# mezzanine_card.net
KiCad netlist of a schematic drawn in Altium Designer
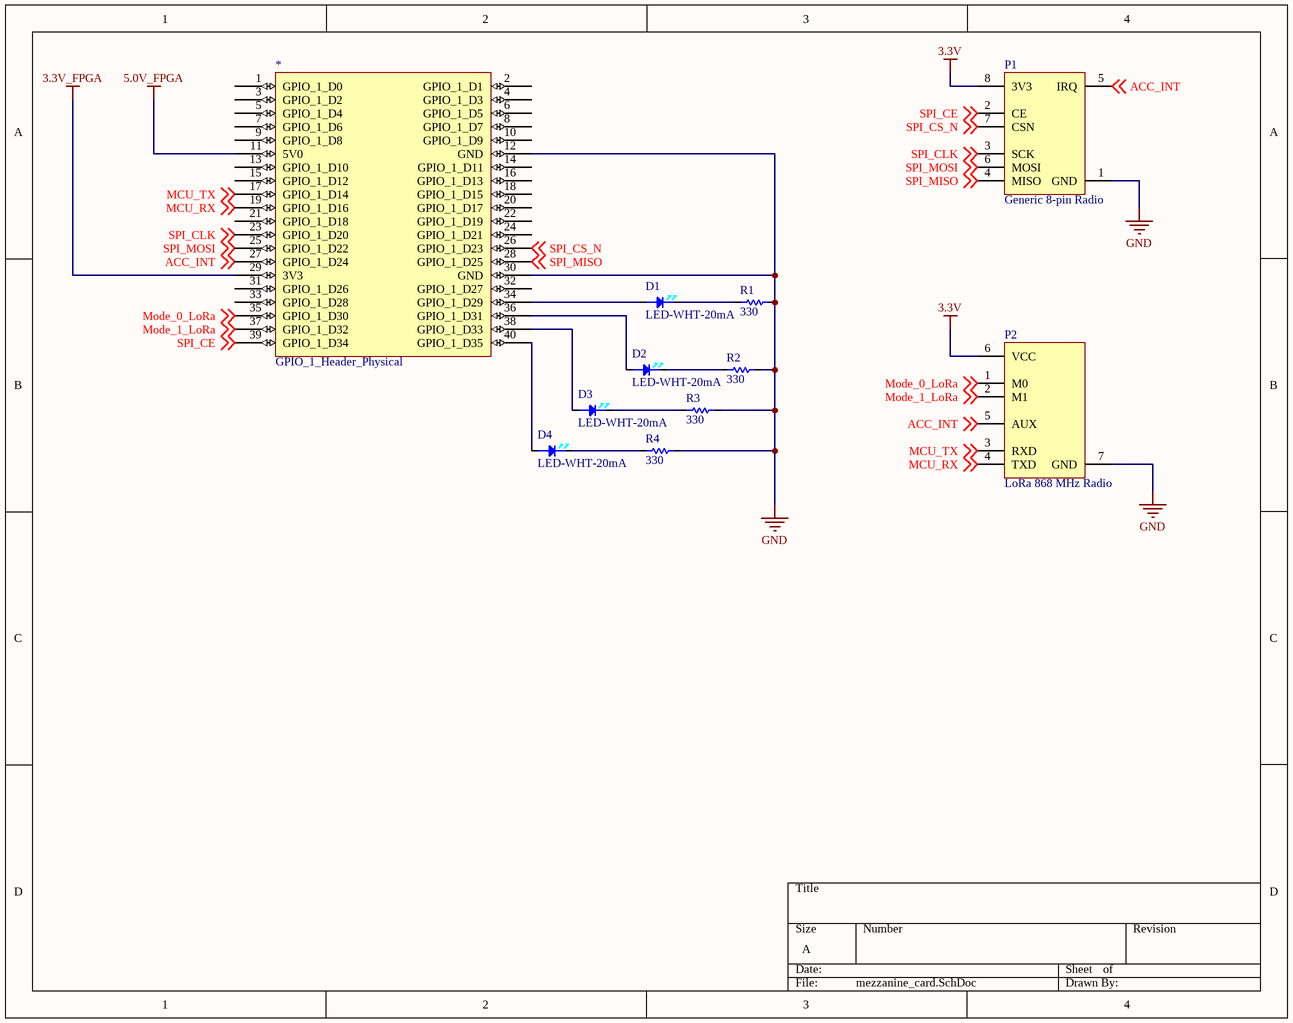
[diagram p0: mezzanine_card.SchDoc]

(export (version "E")
  (design (tool "Eeschema 10.0.6"))
  (components
    (comp (ref "*")
      (value "GPIO_1_Header_Physical")
      (libsource (lib "de0_soc") (part "GPIO_1_Header_Physical"))
    )
    (comp (ref "D1")
      (value "LED-WHT-20mA")
      (footprint "LED-0805")
      (description "2.2V, 0805")
      (libsource (lib "passive") (part "LED-WHT-20mA"))
    )
    (comp (ref "D2")
      (value "LED-WHT-20mA")
      (footprint "LED-0805")
      (description "2.2V, 0805")
      (libsource (lib "passive") (part "LED-WHT-20mA"))
    )
    (comp (ref "D3")
      (value "LED-WHT-20mA")
      (footprint "LED-0805")
      (description "2.2V, 0805")
      (libsource (lib "passive") (part "LED-WHT-20mA"))
    )
    (comp (ref "D4")
      (value "LED-WHT-20mA")
      (footprint "LED-0805")
      (description "2.2V, 0805")
      (libsource (lib "passive") (part "LED-WHT-20mA"))
    )
    (comp (ref "P1")
      (value "Generic 8-pin Radio")
      (footprint "2x4 Radio")
      (description "SPI Interface, 0.1\" Pitch 2x4")
      (libsource (lib "connector") (part "Generic 8-pin Radio"))
    )
    (comp (ref "P2")
      (value "LoRa 868 MHz Radio")
      (footprint "LoRa Breakout")
      (description "UART Interface, 0.1\" Pitch")
      (libsource (lib "connector") (part "868 MHz SX1276 LoRa Breakout"))
    )
    (comp (ref "R1")
      (value "330")
      (footprint "RES-0805")
      (description "0805")
      (libsource (lib "passive") (part "RES-330-1/8W"))
    )
    (comp (ref "R2")
      (value "330")
      (footprint "RES-0805")
      (description "0805")
      (libsource (lib "passive") (part "RES-330-1/8W"))
    )
    (comp (ref "R3")
      (value "330")
      (footprint "RES-0805")
      (description "0805")
      (libsource (lib "passive") (part "RES-330-1/8W"))
    )
    (comp (ref "R4")
      (value "330")
      (footprint "RES-0805")
      (description "0805")
      (libsource (lib "passive") (part "RES-330-1/8W"))
    )
  )
  (nets
    (net (code "1") (name "3.3V") (class "Default")
      (node (ref "P1") (pin "8") (pinfunction "3V3_8") (pintype "passive"))
      (node (ref "P2") (pin "6") (pinfunction "VCC_6") (pintype "passive"))
    )
    (net (code "2") (name "3.3V_FPGA") (class "Default")
      (node (ref "*") (pin "29") (pinfunction "3V3_29") (pintype "bidirectional"))
    )
    (net (code "3") (name "5.0V_FPGA") (class "Default")
      (node (ref "*") (pin "11") (pinfunction "5V0_11") (pintype "bidirectional"))
    )
    (net (code "4") (name "ACC_INT") (class "Default")
      (node (ref "*") (pin "27") (pinfunction "GPIO_1_D24_27") (pintype "bidirectional"))
      (node (ref "P1") (pin "5") (pinfunction "IRQ_5") (pintype "passive"))
      (node (ref "P2") (pin "5") (pinfunction "AUX_5") (pintype "passive"))
    )
    (net (code "5") (name "GND") (class "Default")
      (node (ref "*") (pin "12") (pinfunction "GND_12") (pintype "bidirectional"))
      (node (ref "*") (pin "30") (pinfunction "GND_30") (pintype "bidirectional"))
      (node (ref "P1") (pin "1") (pinfunction "GND_1") (pintype "passive"))
      (node (ref "P2") (pin "7") (pinfunction "GND_7") (pintype "passive"))
      (node (ref "R1") (pin "2") (pinfunction "2_2") (pintype "passive"))
      (node (ref "R2") (pin "2") (pinfunction "2_2") (pintype "passive"))
      (node (ref "R3") (pin "2") (pinfunction "2_2") (pintype "passive"))
      (node (ref "R4") (pin "2") (pinfunction "2_2") (pintype "passive"))
    )
    (net (code "6") (name "MCU_RX") (class "Default")
      (node (ref "*") (pin "19") (pinfunction "GPIO_1_D16_19") (pintype "bidirectional"))
      (node (ref "P2") (pin "4") (pinfunction "TXD_4") (pintype "passive"))
    )
    (net (code "7") (name "MCU_TX") (class "Default")
      (node (ref "*") (pin "17") (pinfunction "GPIO_1_D14_17") (pintype "bidirectional"))
      (node (ref "P2") (pin "3") (pinfunction "RXD_3") (pintype "passive"))
    )
    (net (code "8") (name "Mode_0_LoRa") (class "Default")
      (node (ref "*") (pin "35") (pinfunction "GPIO_1_D30_35") (pintype "bidirectional"))
      (node (ref "P2") (pin "1") (pinfunction "M0_1") (pintype "passive"))
    )
    (net (code "9") (name "Mode_1_LoRa") (class "Default")
      (node (ref "*") (pin "37") (pinfunction "GPIO_1_D32_37") (pintype "bidirectional"))
      (node (ref "P2") (pin "2") (pinfunction "M1_2") (pintype "passive"))
    )
    (net (code "10") (name "Net-(*-GPIO_1_D29)") (class "Default")
      (node (ref "*") (pin "34") (pinfunction "GPIO_1_D29_34") (pintype "bidirectional"))
      (node (ref "D1") (pin "1") (pinfunction "CT_1") (pintype "passive"))
    )
    (net (code "11") (name "Net-(*-GPIO_1_D31)") (class "Default")
      (node (ref "*") (pin "36") (pinfunction "GPIO_1_D31_36") (pintype "bidirectional"))
      (node (ref "D2") (pin "1") (pinfunction "CT_1") (pintype "passive"))
    )
    (net (code "12") (name "Net-(*-GPIO_1_D33)") (class "Default")
      (node (ref "*") (pin "38") (pinfunction "GPIO_1_D33_38") (pintype "bidirectional"))
      (node (ref "D3") (pin "1") (pinfunction "CT_1") (pintype "passive"))
    )
    (net (code "13") (name "Net-(*-GPIO_1_D35)") (class "Default")
      (node (ref "*") (pin "40") (pinfunction "GPIO_1_D35_40") (pintype "bidirectional"))
      (node (ref "D4") (pin "1") (pinfunction "CT_1") (pintype "passive"))
    )
    (net (code "14") (name "Net-(D1-AN)") (class "Default")
      (node (ref "D1") (pin "2") (pinfunction "AN_2") (pintype "passive"))
      (node (ref "R1") (pin "1") (pinfunction "1_1") (pintype "passive"))
    )
    (net (code "15") (name "Net-(D2-AN)") (class "Default")
      (node (ref "D2") (pin "2") (pinfunction "AN_2") (pintype "passive"))
      (node (ref "R2") (pin "1") (pinfunction "1_1") (pintype "passive"))
    )
    (net (code "16") (name "Net-(D3-AN)") (class "Default")
      (node (ref "D3") (pin "2") (pinfunction "AN_2") (pintype "passive"))
      (node (ref "R3") (pin "1") (pinfunction "1_1") (pintype "passive"))
    )
    (net (code "17") (name "Net-(D4-AN)") (class "Default")
      (node (ref "D4") (pin "2") (pinfunction "AN_2") (pintype "passive"))
      (node (ref "R4") (pin "1") (pinfunction "1_1") (pintype "passive"))
    )
    (net (code "18") (name "SPI_CE") (class "Default")
      (node (ref "*") (pin "39") (pinfunction "GPIO_1_D34_39") (pintype "bidirectional"))
      (node (ref "P1") (pin "2") (pinfunction "CE_2") (pintype "passive"))
    )
    (net (code "19") (name "SPI_CLK") (class "Default")
      (node (ref "*") (pin "23") (pinfunction "GPIO_1_D20_23") (pintype "bidirectional"))
      (node (ref "P1") (pin "3") (pinfunction "SCK_3") (pintype "passive"))
    )
    (net (code "20") (name "SPI_CS_N") (class "Default")
      (node (ref "*") (pin "26") (pinfunction "GPIO_1_D23_26") (pintype "bidirectional"))
      (node (ref "P1") (pin "7") (pinfunction "CSN_7") (pintype "passive"))
    )
    (net (code "21") (name "SPI_MISO") (class "Default")
      (node (ref "*") (pin "28") (pinfunction "GPIO_1_D25_28") (pintype "bidirectional"))
      (node (ref "P1") (pin "4") (pinfunction "MISO_4") (pintype "passive"))
    )
    (net (code "22") (name "SPI_MOSI") (class "Default")
      (node (ref "*") (pin "25") (pinfunction "GPIO_1_D22_25") (pintype "bidirectional"))
      (node (ref "P1") (pin "6") (pinfunction "MOSI_6") (pintype "passive"))
    )
    (net (code "23") (name "unconnected-(*-GPIO_1_D0-Pad1)") (class "Default")
      (node (ref "*") (pin "1") (pinfunction "GPIO_1_D0_1") (pintype "bidirectional"))
    )
    (net (code "24") (name "unconnected-(*-GPIO_1_D1-Pad2)") (class "Default")
      (node (ref "*") (pin "2") (pinfunction "GPIO_1_D1_2") (pintype "bidirectional"))
    )
    (net (code "25") (name "unconnected-(*-GPIO_1_D2-Pad3)") (class "Default")
      (node (ref "*") (pin "3") (pinfunction "GPIO_1_D2_3") (pintype "bidirectional"))
    )
    (net (code "26") (name "unconnected-(*-GPIO_1_D3-Pad4)") (class "Default")
      (node (ref "*") (pin "4") (pinfunction "GPIO_1_D3_4") (pintype "bidirectional"))
    )
    (net (code "27") (name "unconnected-(*-GPIO_1_D4-Pad5)") (class "Default")
      (node (ref "*") (pin "5") (pinfunction "GPIO_1_D4_5") (pintype "bidirectional"))
    )
    (net (code "28") (name "unconnected-(*-GPIO_1_D5-Pad6)") (class "Default")
      (node (ref "*") (pin "6") (pinfunction "GPIO_1_D5_6") (pintype "bidirectional"))
    )
    (net (code "29") (name "unconnected-(*-GPIO_1_D6-Pad7)") (class "Default")
      (node (ref "*") (pin "7") (pinfunction "GPIO_1_D6_7") (pintype "bidirectional"))
    )
    (net (code "30") (name "unconnected-(*-GPIO_1_D7-Pad8)") (class "Default")
      (node (ref "*") (pin "8") (pinfunction "GPIO_1_D7_8") (pintype "bidirectional"))
    )
    (net (code "31") (name "unconnected-(*-GPIO_1_D8-Pad9)") (class "Default")
      (node (ref "*") (pin "9") (pinfunction "GPIO_1_D8_9") (pintype "bidirectional"))
    )
    (net (code "32") (name "unconnected-(*-GPIO_1_D9-Pad10)") (class "Default")
      (node (ref "*") (pin "10") (pinfunction "GPIO_1_D9_10") (pintype "bidirectional"))
    )
    (net (code "33") (name "unconnected-(*-GPIO_1_D10-Pad13)") (class "Default")
      (node (ref "*") (pin "13") (pinfunction "GPIO_1_D10_13") (pintype "bidirectional"))
    )
    (net (code "34") (name "unconnected-(*-GPIO_1_D11-Pad14)") (class "Default")
      (node (ref "*") (pin "14") (pinfunction "GPIO_1_D11_14") (pintype "bidirectional"))
    )
    (net (code "35") (name "unconnected-(*-GPIO_1_D12-Pad15)") (class "Default")
      (node (ref "*") (pin "15") (pinfunction "GPIO_1_D12_15") (pintype "bidirectional"))
    )
    (net (code "36") (name "unconnected-(*-GPIO_1_D13-Pad16)") (class "Default")
      (node (ref "*") (pin "16") (pinfunction "GPIO_1_D13_16") (pintype "bidirectional"))
    )
    (net (code "37") (name "unconnected-(*-GPIO_1_D15-Pad18)") (class "Default")
      (node (ref "*") (pin "18") (pinfunction "GPIO_1_D15_18") (pintype "bidirectional"))
    )
    (net (code "38") (name "unconnected-(*-GPIO_1_D17-Pad20)") (class "Default")
      (node (ref "*") (pin "20") (pinfunction "GPIO_1_D17_20") (pintype "bidirectional"))
    )
    (net (code "39") (name "unconnected-(*-GPIO_1_D18-Pad21)") (class "Default")
      (node (ref "*") (pin "21") (pinfunction "GPIO_1_D18_21") (pintype "bidirectional"))
    )
    (net (code "40") (name "unconnected-(*-GPIO_1_D19-Pad22)") (class "Default")
      (node (ref "*") (pin "22") (pinfunction "GPIO_1_D19_22") (pintype "bidirectional"))
    )
    (net (code "41") (name "unconnected-(*-GPIO_1_D21-Pad24)") (class "Default")
      (node (ref "*") (pin "24") (pinfunction "GPIO_1_D21_24") (pintype "bidirectional"))
    )
    (net (code "42") (name "unconnected-(*-GPIO_1_D26-Pad31)") (class "Default")
      (node (ref "*") (pin "31") (pinfunction "GPIO_1_D26_31") (pintype "bidirectional"))
    )
    (net (code "43") (name "unconnected-(*-GPIO_1_D27-Pad32)") (class "Default")
      (node (ref "*") (pin "32") (pinfunction "GPIO_1_D27_32") (pintype "bidirectional"))
    )
    (net (code "44") (name "unconnected-(*-GPIO_1_D28-Pad33)") (class "Default")
      (node (ref "*") (pin "33") (pinfunction "GPIO_1_D28_33") (pintype "bidirectional"))
    )
  )
)
